# IO_board-ha-v4.net
KiCad netlist of a schematic drawn in EAGLE
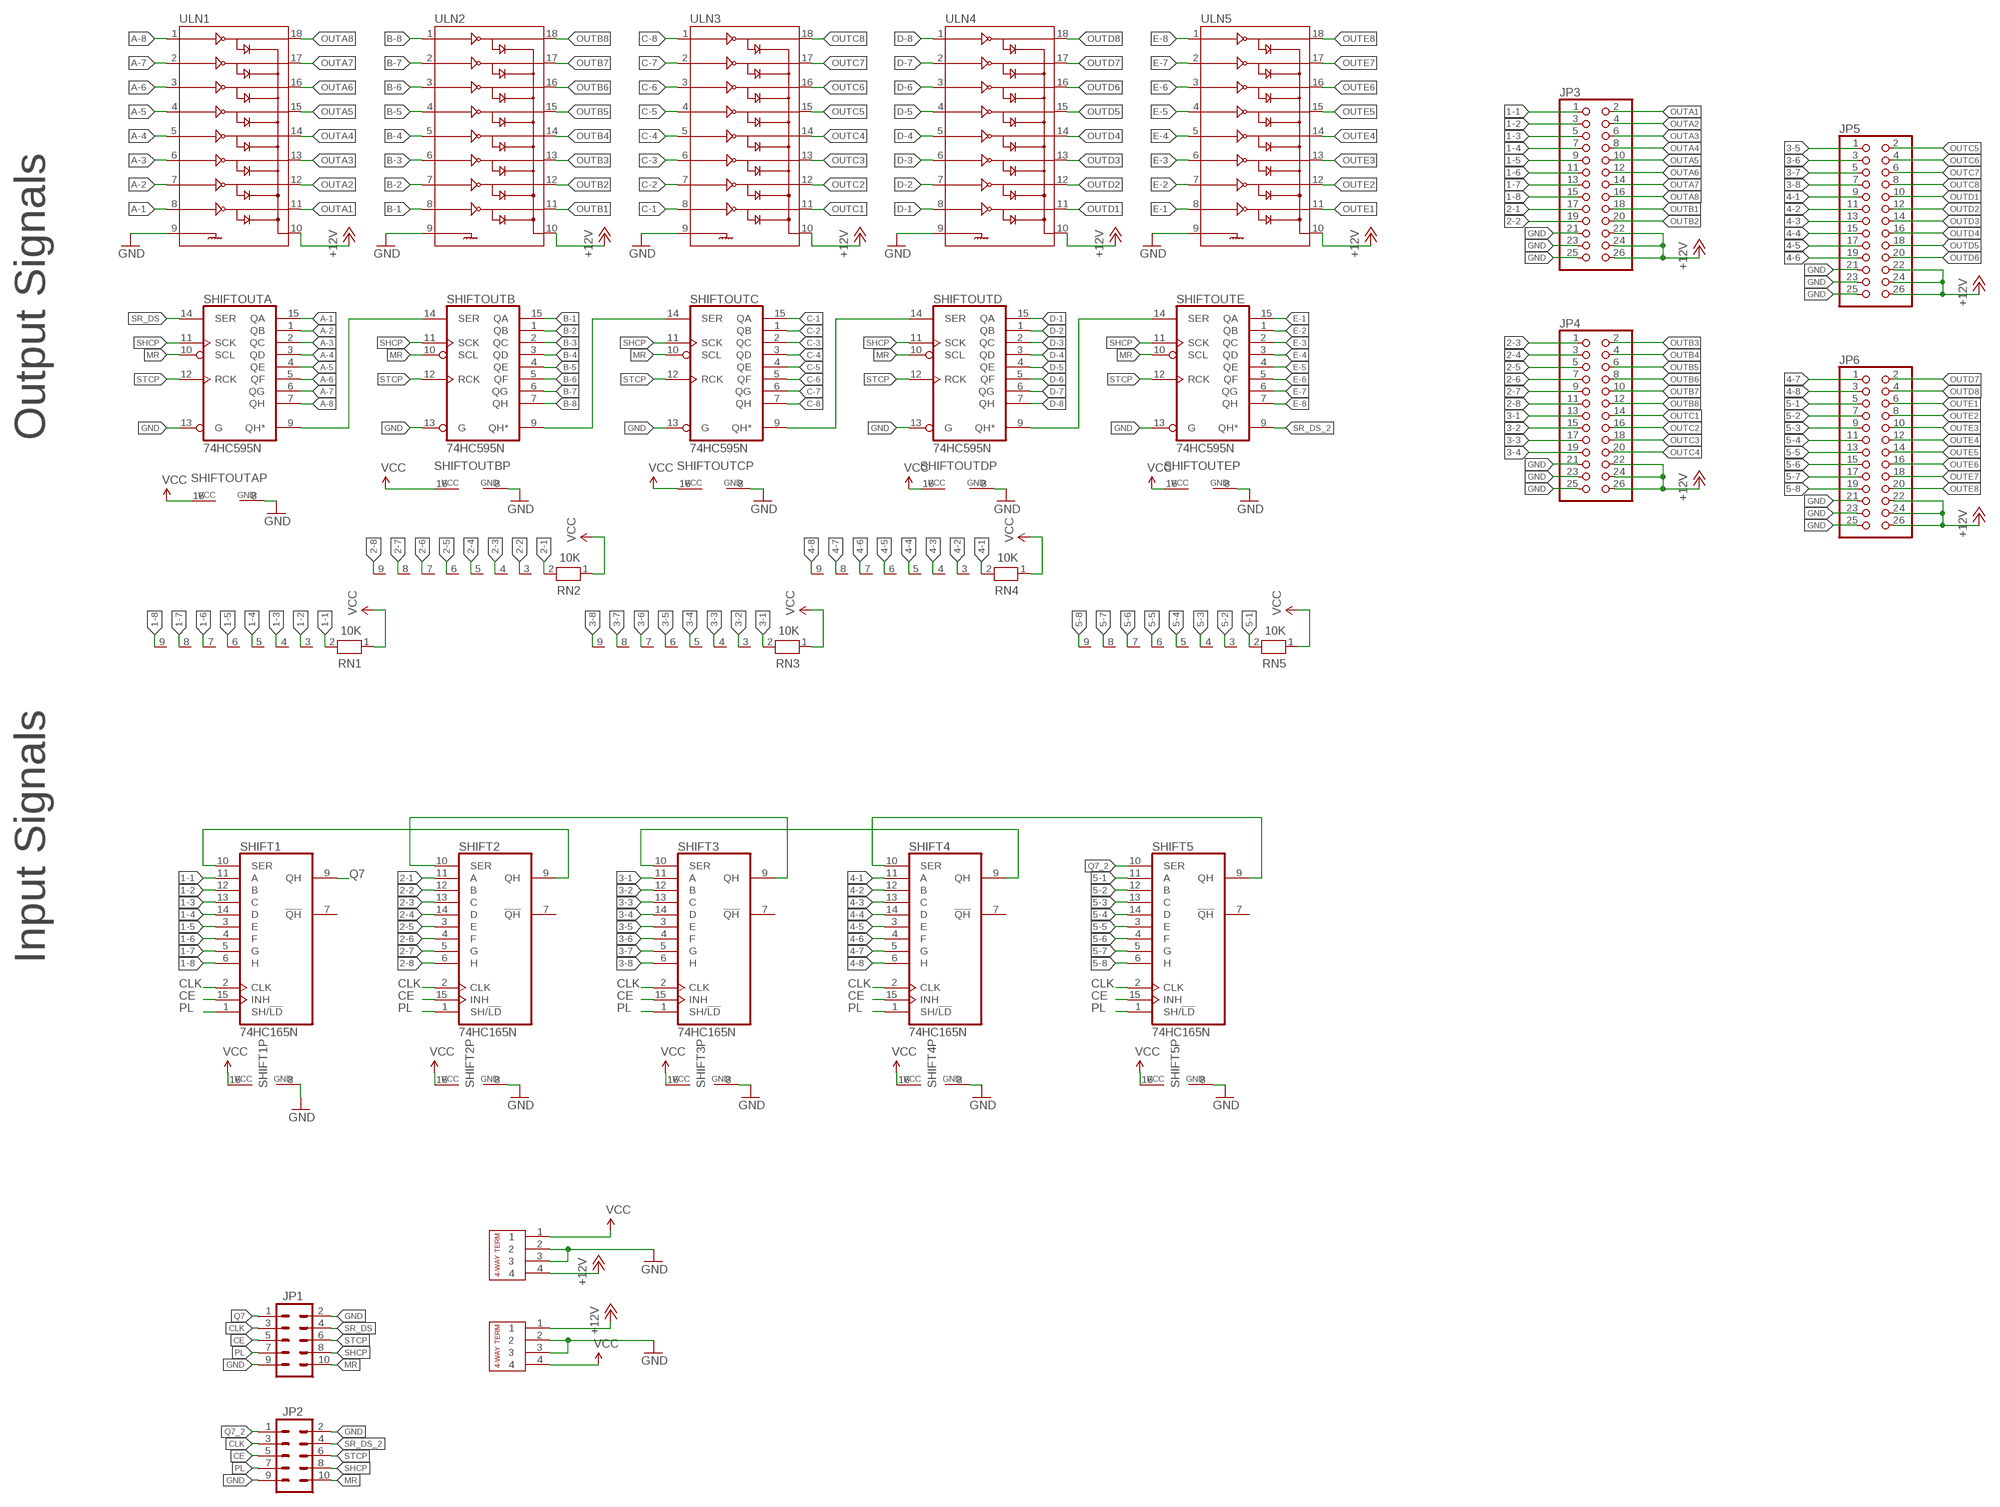
[diagram p0: schematic, sheet 1]

(export (version "E")
  (design (tool "Eeschema 10.0.6"))
  (components
    (comp (ref "J1")
      (value "4-PIN-CON-1759017")
      (footprint "eagle-import:4-PIN-CON-1759017")
      (libsource (lib "eagle-import") (part "4-PIN-CON-1759017"))
    )
    (comp (ref "J2")
      (value "4-PIN-CON-1759017")
      (footprint "eagle-import:4-PIN-CON-1759017")
      (libsource (lib "eagle-import") (part "4-PIN-CON-1759017"))
    )
    (comp (ref "JP1")
      (value "M05X2SHD")
      (footprint "eagle-import:2X5-SHROUDED")
      (libsource (lib "eagle-import") (part "M05X2SHD"))
    )
    (comp (ref "JP2")
      (value "M05X2SHD")
      (footprint "eagle-import:2X5-SHROUDED")
      (libsource (lib "eagle-import") (part "M05X2SHD"))
    )
    (comp (ref "JP3")
      (value "PINHD-2X13")
      (footprint "eagle-import:2X13")
      (libsource (lib "eagle-import") (part "PINHD-2X13"))
    )
    (comp (ref "JP4")
      (value "PINHD-2X13")
      (footprint "eagle-import:2X13")
      (libsource (lib "eagle-import") (part "PINHD-2X13"))
    )
    (comp (ref "JP5")
      (value "PINHD-2X13")
      (footprint "eagle-import:2X13")
      (libsource (lib "eagle-import") (part "PINHD-2X13"))
    )
    (comp (ref "JP6")
      (value "PINHD-2X13")
      (footprint "eagle-import:2X13")
      (libsource (lib "eagle-import") (part "PINHD-2X13"))
    )
    (comp (ref "RN1")
      (value "10K")
      (footprint "eagle-import:RN-9")
      (libsource (lib "eagle-import") (part "RN08"))
    )
    (comp (ref "RN2")
      (value "10K")
      (footprint "eagle-import:RN-9")
      (libsource (lib "eagle-import") (part "RN08"))
    )
    (comp (ref "RN3")
      (value "10K")
      (footprint "eagle-import:RN-9")
      (libsource (lib "eagle-import") (part "RN08"))
    )
    (comp (ref "RN4")
      (value "10K")
      (footprint "eagle-import:RN-9")
      (libsource (lib "eagle-import") (part "RN08"))
    )
    (comp (ref "RN5")
      (value "10K")
      (footprint "eagle-import:RN-9")
      (libsource (lib "eagle-import") (part "RN08"))
    )
    (comp (ref "SHIFT1")
      (value "74HC165N")
      (footprint "eagle-import:DIL16")
      (libsource (lib "eagle-import") (part "74165NHC"))
    )
    (comp (ref "SHIFT2")
      (value "74HC165N")
      (footprint "eagle-import:DIL16")
      (libsource (lib "eagle-import") (part "74165NHC"))
    )
    (comp (ref "SHIFT3")
      (value "74HC165N")
      (footprint "eagle-import:DIL16")
      (libsource (lib "eagle-import") (part "74165NHC"))
    )
    (comp (ref "SHIFT4")
      (value "74HC165N")
      (footprint "eagle-import:DIL16")
      (libsource (lib "eagle-import") (part "74165NHC"))
    )
    (comp (ref "SHIFT5")
      (value "74HC165N")
      (footprint "eagle-import:DIL16")
      (libsource (lib "eagle-import") (part "74165NHC"))
    )
    (comp (ref "SHIFTOUTA")
      (value "74HC595N")
      (footprint "eagle-import:DIL16")
      (libsource (lib "eagle-import") (part "74595NHC"))
    )
    (comp (ref "SHIFTOUTB")
      (value "74HC595N")
      (footprint "eagle-import:DIL16")
      (libsource (lib "eagle-import") (part "74595NHC"))
    )
    (comp (ref "SHIFTOUTC")
      (value "74HC595N")
      (footprint "eagle-import:DIL16")
      (libsource (lib "eagle-import") (part "74595NHC"))
    )
    (comp (ref "SHIFTOUTD")
      (value "74HC595N")
      (footprint "eagle-import:DIL16")
      (libsource (lib "eagle-import") (part "74595NHC"))
    )
    (comp (ref "SHIFTOUTE")
      (value "74HC595N")
      (footprint "eagle-import:DIL16")
      (libsource (lib "eagle-import") (part "74595NHC"))
    )
    (comp (ref "ULN1")
      (value "ULN2803DIP")
      (footprint "eagle-import:DIL18")
      (libsource (lib "eagle-import") (part "ULN2803DIP"))
    )
    (comp (ref "ULN2")
      (value "ULN2803DIP")
      (footprint "eagle-import:DIL18")
      (libsource (lib "eagle-import") (part "ULN2803DIP"))
    )
    (comp (ref "ULN3")
      (value "ULN2803DIP")
      (footprint "eagle-import:DIL18")
      (libsource (lib "eagle-import") (part "ULN2803DIP"))
    )
    (comp (ref "ULN4")
      (value "ULN2803DIP")
      (footprint "eagle-import:DIL18")
      (libsource (lib "eagle-import") (part "ULN2803DIP"))
    )
    (comp (ref "ULN5")
      (value "ULN2803DIP")
      (footprint "eagle-import:DIL18")
      (libsource (lib "eagle-import") (part "ULN2803DIP"))
    )
  )
  (nets
    (net (code "1") (name "+12V") (class "Default")
      (node (ref "J1") (pin "4") (pinfunction "4_4") (pintype "bidirectional"))
      (node (ref "J2") (pin "1") (pinfunction "1_1") (pintype "bidirectional"))
      (node (ref "JP3") (pin "22") (pinfunction "22_22") (pintype "passive"))
      (node (ref "JP3") (pin "24") (pinfunction "24_24") (pintype "passive"))
      (node (ref "JP3") (pin "26") (pinfunction "26_26") (pintype "passive"))
      (node (ref "JP4") (pin "22") (pinfunction "22_22") (pintype "passive"))
      (node (ref "JP4") (pin "24") (pinfunction "24_24") (pintype "passive"))
      (node (ref "JP4") (pin "26") (pinfunction "26_26") (pintype "passive"))
      (node (ref "JP5") (pin "22") (pinfunction "22_22") (pintype "passive"))
      (node (ref "JP5") (pin "24") (pinfunction "24_24") (pintype "passive"))
      (node (ref "JP5") (pin "26") (pinfunction "26_26") (pintype "passive"))
      (node (ref "JP6") (pin "22") (pinfunction "22_22") (pintype "passive"))
      (node (ref "JP6") (pin "24") (pinfunction "24_24") (pintype "passive"))
      (node (ref "JP6") (pin "26") (pinfunction "26_26") (pintype "passive"))
      (node (ref "ULN1") (pin "10") (pinfunction "10_10") (pintype "bidirectional"))
      (node (ref "ULN2") (pin "10") (pinfunction "10_10") (pintype "bidirectional"))
      (node (ref "ULN3") (pin "10") (pinfunction "10_10") (pintype "bidirectional"))
      (node (ref "ULN4") (pin "10") (pinfunction "10_10") (pintype "bidirectional"))
      (node (ref "ULN5") (pin "10") (pinfunction "10_10") (pintype "bidirectional"))
    )
    (net (code "2") (name "1-1") (class "Default")
      (node (ref "JP3") (pin "1") (pinfunction "1_1") (pintype "passive"))
      (node (ref "RN1") (pin "2") (pinfunction "2_2") (pintype "passive"))
      (node (ref "SHIFT1") (pin "11") (pinfunction "A_11") (pintype "input"))
    )
    (net (code "3") (name "1-2") (class "Default")
      (node (ref "JP3") (pin "3") (pinfunction "3_3") (pintype "passive"))
      (node (ref "RN1") (pin "3") (pinfunction "3_3") (pintype "passive"))
      (node (ref "SHIFT1") (pin "12") (pinfunction "B_12") (pintype "input"))
    )
    (net (code "4") (name "1-3") (class "Default")
      (node (ref "JP3") (pin "5") (pinfunction "5_5") (pintype "passive"))
      (node (ref "RN1") (pin "4") (pinfunction "4_4") (pintype "passive"))
      (node (ref "SHIFT1") (pin "13") (pinfunction "C_13") (pintype "input"))
    )
    (net (code "5") (name "1-4") (class "Default")
      (node (ref "JP3") (pin "7") (pinfunction "7_7") (pintype "passive"))
      (node (ref "RN1") (pin "5") (pinfunction "5_5") (pintype "passive"))
      (node (ref "SHIFT1") (pin "14") (pinfunction "D_14") (pintype "input"))
    )
    (net (code "6") (name "1-5") (class "Default")
      (node (ref "JP3") (pin "9") (pinfunction "9_9") (pintype "passive"))
      (node (ref "RN1") (pin "6") (pinfunction "6_6") (pintype "passive"))
      (node (ref "SHIFT1") (pin "3") (pinfunction "E_3") (pintype "input"))
    )
    (net (code "7") (name "1-6") (class "Default")
      (node (ref "JP3") (pin "11") (pinfunction "11_11") (pintype "passive"))
      (node (ref "RN1") (pin "7") (pinfunction "7_7") (pintype "passive"))
      (node (ref "SHIFT1") (pin "4") (pinfunction "F_4") (pintype "input"))
    )
    (net (code "8") (name "1-7") (class "Default")
      (node (ref "JP3") (pin "13") (pinfunction "13_13") (pintype "passive"))
      (node (ref "RN1") (pin "8") (pinfunction "8_8") (pintype "passive"))
      (node (ref "SHIFT1") (pin "5") (pinfunction "G_5") (pintype "input"))
    )
    (net (code "9") (name "1-8") (class "Default")
      (node (ref "JP3") (pin "15") (pinfunction "15_15") (pintype "passive"))
      (node (ref "RN1") (pin "9") (pinfunction "9_9") (pintype "passive"))
      (node (ref "SHIFT1") (pin "6") (pinfunction "H_6") (pintype "input"))
    )
    (net (code "10") (name "2-1") (class "Default")
      (node (ref "JP3") (pin "17") (pinfunction "17_17") (pintype "passive"))
      (node (ref "RN2") (pin "2") (pinfunction "2_2") (pintype "passive"))
      (node (ref "SHIFT2") (pin "11") (pinfunction "A_11") (pintype "input"))
    )
    (net (code "11") (name "2-2") (class "Default")
      (node (ref "JP3") (pin "19") (pinfunction "19_19") (pintype "passive"))
      (node (ref "RN2") (pin "3") (pinfunction "3_3") (pintype "passive"))
      (node (ref "SHIFT2") (pin "12") (pinfunction "B_12") (pintype "input"))
    )
    (net (code "12") (name "2-3") (class "Default")
      (node (ref "JP4") (pin "1") (pinfunction "1_1") (pintype "passive"))
      (node (ref "RN2") (pin "4") (pinfunction "4_4") (pintype "passive"))
      (node (ref "SHIFT2") (pin "13") (pinfunction "C_13") (pintype "input"))
    )
    (net (code "13") (name "2-4") (class "Default")
      (node (ref "JP4") (pin "3") (pinfunction "3_3") (pintype "passive"))
      (node (ref "RN2") (pin "5") (pinfunction "5_5") (pintype "passive"))
      (node (ref "SHIFT2") (pin "14") (pinfunction "D_14") (pintype "input"))
    )
    (net (code "14") (name "2-5") (class "Default")
      (node (ref "JP4") (pin "5") (pinfunction "5_5") (pintype "passive"))
      (node (ref "RN2") (pin "6") (pinfunction "6_6") (pintype "passive"))
      (node (ref "SHIFT2") (pin "3") (pinfunction "E_3") (pintype "input"))
    )
    (net (code "15") (name "2-6") (class "Default")
      (node (ref "JP4") (pin "7") (pinfunction "7_7") (pintype "passive"))
      (node (ref "RN2") (pin "7") (pinfunction "7_7") (pintype "passive"))
      (node (ref "SHIFT2") (pin "4") (pinfunction "F_4") (pintype "input"))
    )
    (net (code "16") (name "2-7") (class "Default")
      (node (ref "JP4") (pin "9") (pinfunction "9_9") (pintype "passive"))
      (node (ref "RN2") (pin "8") (pinfunction "8_8") (pintype "passive"))
      (node (ref "SHIFT2") (pin "5") (pinfunction "G_5") (pintype "input"))
    )
    (net (code "17") (name "2-8") (class "Default")
      (node (ref "JP4") (pin "11") (pinfunction "11_11") (pintype "passive"))
      (node (ref "RN2") (pin "9") (pinfunction "9_9") (pintype "passive"))
      (node (ref "SHIFT2") (pin "6") (pinfunction "H_6") (pintype "input"))
    )
    (net (code "18") (name "3-1") (class "Default")
      (node (ref "JP4") (pin "13") (pinfunction "13_13") (pintype "passive"))
      (node (ref "RN3") (pin "2") (pinfunction "2_2") (pintype "passive"))
      (node (ref "SHIFT3") (pin "11") (pinfunction "A_11") (pintype "input"))
    )
    (net (code "19") (name "3-2") (class "Default")
      (node (ref "JP4") (pin "15") (pinfunction "15_15") (pintype "passive"))
      (node (ref "RN3") (pin "3") (pinfunction "3_3") (pintype "passive"))
      (node (ref "SHIFT3") (pin "12") (pinfunction "B_12") (pintype "input"))
    )
    (net (code "20") (name "3-3") (class "Default")
      (node (ref "JP4") (pin "17") (pinfunction "17_17") (pintype "passive"))
      (node (ref "RN3") (pin "4") (pinfunction "4_4") (pintype "passive"))
      (node (ref "SHIFT3") (pin "13") (pinfunction "C_13") (pintype "input"))
    )
    (net (code "21") (name "3-4") (class "Default")
      (node (ref "JP4") (pin "19") (pinfunction "19_19") (pintype "passive"))
      (node (ref "RN3") (pin "5") (pinfunction "5_5") (pintype "passive"))
      (node (ref "SHIFT3") (pin "14") (pinfunction "D_14") (pintype "input"))
    )
    (net (code "22") (name "3-5") (class "Default")
      (node (ref "JP5") (pin "1") (pinfunction "1_1") (pintype "passive"))
      (node (ref "RN3") (pin "6") (pinfunction "6_6") (pintype "passive"))
      (node (ref "SHIFT3") (pin "3") (pinfunction "E_3") (pintype "input"))
    )
    (net (code "23") (name "3-6") (class "Default")
      (node (ref "JP5") (pin "3") (pinfunction "3_3") (pintype "passive"))
      (node (ref "RN3") (pin "7") (pinfunction "7_7") (pintype "passive"))
      (node (ref "SHIFT3") (pin "4") (pinfunction "F_4") (pintype "input"))
    )
    (net (code "24") (name "3-7") (class "Default")
      (node (ref "JP5") (pin "5") (pinfunction "5_5") (pintype "passive"))
      (node (ref "RN3") (pin "8") (pinfunction "8_8") (pintype "passive"))
      (node (ref "SHIFT3") (pin "5") (pinfunction "G_5") (pintype "input"))
    )
    (net (code "25") (name "3-8") (class "Default")
      (node (ref "JP5") (pin "7") (pinfunction "7_7") (pintype "passive"))
      (node (ref "RN3") (pin "9") (pinfunction "9_9") (pintype "passive"))
      (node (ref "SHIFT3") (pin "6") (pinfunction "H_6") (pintype "input"))
    )
    (net (code "26") (name "4-1") (class "Default")
      (node (ref "JP5") (pin "9") (pinfunction "9_9") (pintype "passive"))
      (node (ref "RN4") (pin "2") (pinfunction "2_2") (pintype "passive"))
      (node (ref "SHIFT4") (pin "11") (pinfunction "A_11") (pintype "input"))
    )
    (net (code "27") (name "4-2") (class "Default")
      (node (ref "JP5") (pin "11") (pinfunction "11_11") (pintype "passive"))
      (node (ref "RN4") (pin "3") (pinfunction "3_3") (pintype "passive"))
      (node (ref "SHIFT4") (pin "12") (pinfunction "B_12") (pintype "input"))
    )
    (net (code "28") (name "4-3") (class "Default")
      (node (ref "JP5") (pin "13") (pinfunction "13_13") (pintype "passive"))
      (node (ref "RN4") (pin "4") (pinfunction "4_4") (pintype "passive"))
      (node (ref "SHIFT4") (pin "13") (pinfunction "C_13") (pintype "input"))
    )
    (net (code "29") (name "4-4") (class "Default")
      (node (ref "JP5") (pin "15") (pinfunction "15_15") (pintype "passive"))
      (node (ref "RN4") (pin "5") (pinfunction "5_5") (pintype "passive"))
      (node (ref "SHIFT4") (pin "14") (pinfunction "D_14") (pintype "input"))
    )
    (net (code "30") (name "4-5") (class "Default")
      (node (ref "JP5") (pin "17") (pinfunction "17_17") (pintype "passive"))
      (node (ref "RN4") (pin "6") (pinfunction "6_6") (pintype "passive"))
      (node (ref "SHIFT4") (pin "3") (pinfunction "E_3") (pintype "input"))
    )
    (net (code "31") (name "4-6") (class "Default")
      (node (ref "JP5") (pin "19") (pinfunction "19_19") (pintype "passive"))
      (node (ref "RN4") (pin "7") (pinfunction "7_7") (pintype "passive"))
      (node (ref "SHIFT4") (pin "4") (pinfunction "F_4") (pintype "input"))
    )
    (net (code "32") (name "4-7") (class "Default")
      (node (ref "JP6") (pin "1") (pinfunction "1_1") (pintype "passive"))
      (node (ref "RN4") (pin "8") (pinfunction "8_8") (pintype "passive"))
      (node (ref "SHIFT4") (pin "5") (pinfunction "G_5") (pintype "input"))
    )
    (net (code "33") (name "4-8") (class "Default")
      (node (ref "JP6") (pin "3") (pinfunction "3_3") (pintype "passive"))
      (node (ref "RN4") (pin "9") (pinfunction "9_9") (pintype "passive"))
      (node (ref "SHIFT4") (pin "6") (pinfunction "H_6") (pintype "input"))
    )
    (net (code "34") (name "5-1") (class "Default")
      (node (ref "JP6") (pin "5") (pinfunction "5_5") (pintype "passive"))
      (node (ref "RN5") (pin "2") (pinfunction "2_2") (pintype "passive"))
      (node (ref "SHIFT5") (pin "11") (pinfunction "A_11") (pintype "input"))
    )
    (net (code "35") (name "5-2") (class "Default")
      (node (ref "JP6") (pin "7") (pinfunction "7_7") (pintype "passive"))
      (node (ref "RN5") (pin "3") (pinfunction "3_3") (pintype "passive"))
      (node (ref "SHIFT5") (pin "12") (pinfunction "B_12") (pintype "input"))
    )
    (net (code "36") (name "5-3") (class "Default")
      (node (ref "JP6") (pin "9") (pinfunction "9_9") (pintype "passive"))
      (node (ref "RN5") (pin "4") (pinfunction "4_4") (pintype "passive"))
      (node (ref "SHIFT5") (pin "13") (pinfunction "C_13") (pintype "input"))
    )
    (net (code "37") (name "5-4") (class "Default")
      (node (ref "JP6") (pin "11") (pinfunction "11_11") (pintype "passive"))
      (node (ref "RN5") (pin "5") (pinfunction "5_5") (pintype "passive"))
      (node (ref "SHIFT5") (pin "14") (pinfunction "D_14") (pintype "input"))
    )
    (net (code "38") (name "5-5") (class "Default")
      (node (ref "JP6") (pin "13") (pinfunction "13_13") (pintype "passive"))
      (node (ref "RN5") (pin "6") (pinfunction "6_6") (pintype "passive"))
      (node (ref "SHIFT5") (pin "3") (pinfunction "E_3") (pintype "input"))
    )
    (net (code "39") (name "5-6") (class "Default")
      (node (ref "JP6") (pin "15") (pinfunction "15_15") (pintype "passive"))
      (node (ref "RN5") (pin "7") (pinfunction "7_7") (pintype "passive"))
      (node (ref "SHIFT5") (pin "4") (pinfunction "F_4") (pintype "input"))
    )
    (net (code "40") (name "5-7") (class "Default")
      (node (ref "JP6") (pin "17") (pinfunction "17_17") (pintype "passive"))
      (node (ref "RN5") (pin "8") (pinfunction "8_8") (pintype "passive"))
      (node (ref "SHIFT5") (pin "5") (pinfunction "G_5") (pintype "input"))
    )
    (net (code "41") (name "5-8") (class "Default")
      (node (ref "JP6") (pin "19") (pinfunction "19_19") (pintype "passive"))
      (node (ref "RN5") (pin "9") (pinfunction "9_9") (pintype "passive"))
      (node (ref "SHIFT5") (pin "6") (pinfunction "H_6") (pintype "input"))
    )
    (net (code "42") (name "A-1") (class "Default")
      (node (ref "SHIFTOUTA") (pin "15") (pinfunction "QA_15") (pintype "tri_state"))
      (node (ref "ULN1") (pin "8") (pinfunction "8_8") (pintype "bidirectional"))
    )
    (net (code "43") (name "A-2") (class "Default")
      (node (ref "SHIFTOUTA") (pin "1") (pinfunction "QB_1") (pintype "tri_state"))
      (node (ref "ULN1") (pin "7") (pinfunction "7_7") (pintype "bidirectional"))
    )
    (net (code "44") (name "A-3") (class "Default")
      (node (ref "SHIFTOUTA") (pin "2") (pinfunction "QC_2") (pintype "tri_state"))
      (node (ref "ULN1") (pin "6") (pinfunction "6_6") (pintype "bidirectional"))
    )
    (net (code "45") (name "A-4") (class "Default")
      (node (ref "SHIFTOUTA") (pin "3") (pinfunction "QD_3") (pintype "tri_state"))
      (node (ref "ULN1") (pin "5") (pinfunction "5_5") (pintype "bidirectional"))
    )
    (net (code "46") (name "A-5") (class "Default")
      (node (ref "SHIFTOUTA") (pin "4") (pinfunction "QE_4") (pintype "tri_state"))
      (node (ref "ULN1") (pin "4") (pinfunction "4_4") (pintype "bidirectional"))
    )
    (net (code "47") (name "A-6") (class "Default")
      (node (ref "SHIFTOUTA") (pin "5") (pinfunction "QF_5") (pintype "tri_state"))
      (node (ref "ULN1") (pin "3") (pinfunction "3_3") (pintype "bidirectional"))
    )
    (net (code "48") (name "A-7") (class "Default")
      (node (ref "SHIFTOUTA") (pin "6") (pinfunction "QG_6") (pintype "tri_state"))
      (node (ref "ULN1") (pin "2") (pinfunction "2_2") (pintype "bidirectional"))
    )
    (net (code "49") (name "A-8") (class "Default")
      (node (ref "SHIFTOUTA") (pin "7") (pinfunction "QH_7") (pintype "tri_state"))
      (node (ref "ULN1") (pin "1") (pinfunction "1_1") (pintype "bidirectional"))
    )
    (net (code "50") (name "B-1") (class "Default")
      (node (ref "SHIFTOUTB") (pin "15") (pinfunction "QA_15") (pintype "tri_state"))
      (node (ref "ULN2") (pin "8") (pinfunction "8_8") (pintype "bidirectional"))
    )
    (net (code "51") (name "B-2") (class "Default")
      (node (ref "SHIFTOUTB") (pin "1") (pinfunction "QB_1") (pintype "tri_state"))
      (node (ref "ULN2") (pin "7") (pinfunction "7_7") (pintype "bidirectional"))
    )
    (net (code "52") (name "B-3") (class "Default")
      (node (ref "SHIFTOUTB") (pin "2") (pinfunction "QC_2") (pintype "tri_state"))
      (node (ref "ULN2") (pin "6") (pinfunction "6_6") (pintype "bidirectional"))
    )
    (net (code "53") (name "B-4") (class "Default")
      (node (ref "SHIFTOUTB") (pin "3") (pinfunction "QD_3") (pintype "tri_state"))
      (node (ref "ULN2") (pin "5") (pinfunction "5_5") (pintype "bidirectional"))
    )
    (net (code "54") (name "B-5") (class "Default")
      (node (ref "SHIFTOUTB") (pin "4") (pinfunction "QE_4") (pintype "tri_state"))
      (node (ref "ULN2") (pin "4") (pinfunction "4_4") (pintype "bidirectional"))
    )
    (net (code "55") (name "B-6") (class "Default")
      (node (ref "SHIFTOUTB") (pin "5") (pinfunction "QF_5") (pintype "tri_state"))
      (node (ref "ULN2") (pin "3") (pinfunction "3_3") (pintype "bidirectional"))
    )
    (net (code "56") (name "B-7") (class "Default")
      (node (ref "SHIFTOUTB") (pin "6") (pinfunction "QG_6") (pintype "tri_state"))
      (node (ref "ULN2") (pin "2") (pinfunction "2_2") (pintype "bidirectional"))
    )
    (net (code "57") (name "B-8") (class "Default")
      (node (ref "SHIFTOUTB") (pin "7") (pinfunction "QH_7") (pintype "tri_state"))
      (node (ref "ULN2") (pin "1") (pinfunction "1_1") (pintype "bidirectional"))
    )
    (net (code "58") (name "C-1") (class "Default")
      (node (ref "SHIFTOUTC") (pin "15") (pinfunction "QA_15") (pintype "tri_state"))
      (node (ref "ULN3") (pin "8") (pinfunction "8_8") (pintype "bidirectional"))
    )
    (net (code "59") (name "C-2") (class "Default")
      (node (ref "SHIFTOUTC") (pin "1") (pinfunction "QB_1") (pintype "tri_state"))
      (node (ref "ULN3") (pin "7") (pinfunction "7_7") (pintype "bidirectional"))
    )
    (net (code "60") (name "C-3") (class "Default")
      (node (ref "SHIFTOUTC") (pin "2") (pinfunction "QC_2") (pintype "tri_state"))
      (node (ref "ULN3") (pin "6") (pinfunction "6_6") (pintype "bidirectional"))
    )
    (net (code "61") (name "C-4") (class "Default")
      (node (ref "SHIFTOUTC") (pin "3") (pinfunction "QD_3") (pintype "tri_state"))
      (node (ref "ULN3") (pin "5") (pinfunction "5_5") (pintype "bidirectional"))
    )
    (net (code "62") (name "C-5") (class "Default")
      (node (ref "SHIFTOUTC") (pin "4") (pinfunction "QE_4") (pintype "tri_state"))
      (node (ref "ULN3") (pin "4") (pinfunction "4_4") (pintype "bidirectional"))
    )
    (net (code "63") (name "C-6") (class "Default")
      (node (ref "SHIFTOUTC") (pin "5") (pinfunction "QF_5") (pintype "tri_state"))
      (node (ref "ULN3") (pin "3") (pinfunction "3_3") (pintype "bidirectional"))
    )
    (net (code "64") (name "C-7") (class "Default")
      (node (ref "SHIFTOUTC") (pin "6") (pinfunction "QG_6") (pintype "tri_state"))
      (node (ref "ULN3") (pin "2") (pinfunction "2_2") (pintype "bidirectional"))
    )
    (net (code "65") (name "C-8") (class "Default")
      (node (ref "SHIFTOUTC") (pin "7") (pinfunction "QH_7") (pintype "tri_state"))
      (node (ref "ULN3") (pin "1") (pinfunction "1_1") (pintype "bidirectional"))
    )
    (net (code "66") (name "CE") (class "Default")
      (node (ref "JP1") (pin "5") (pinfunction "5_5") (pintype "passive"))
      (node (ref "JP2") (pin "5") (pinfunction "5_5") (pintype "passive"))
      (node (ref "SHIFT1") (pin "15") (pinfunction "INH_15") (pintype "input"))
      (node (ref "SHIFT2") (pin "15") (pinfunction "INH_15") (pintype "input"))
      (node (ref "SHIFT3") (pin "15") (pinfunction "INH_15") (pintype "input"))
      (node (ref "SHIFT4") (pin "15") (pinfunction "INH_15") (pintype "input"))
      (node (ref "SHIFT5") (pin "15") (pinfunction "INH_15") (pintype "input"))
    )
    (net (code "67") (name "CLK") (class "Default")
      (node (ref "JP1") (pin "3") (pinfunction "3_3") (pintype "passive"))
      (node (ref "JP2") (pin "3") (pinfunction "3_3") (pintype "passive"))
      (node (ref "SHIFT1") (pin "2") (pinfunction "CLK_2") (pintype "input"))
      (node (ref "SHIFT2") (pin "2") (pinfunction "CLK_2") (pintype "input"))
      (node (ref "SHIFT3") (pin "2") (pinfunction "CLK_2") (pintype "input"))
      (node (ref "SHIFT4") (pin "2") (pinfunction "CLK_2") (pintype "input"))
      (node (ref "SHIFT5") (pin "2") (pinfunction "CLK_2") (pintype "input"))
    )
    (net (code "68") (name "D-1") (class "Default")
      (node (ref "SHIFTOUTD") (pin "15") (pinfunction "QA_15") (pintype "tri_state"))
      (node (ref "ULN4") (pin "8") (pinfunction "8_8") (pintype "bidirectional"))
    )
    (net (code "69") (name "D-2") (class "Default")
      (node (ref "SHIFTOUTD") (pin "1") (pinfunction "QB_1") (pintype "tri_state"))
      (node (ref "ULN4") (pin "7") (pinfunction "7_7") (pintype "bidirectional"))
    )
    (net (code "70") (name "D-3") (class "Default")
      (node (ref "SHIFTOUTD") (pin "2") (pinfunction "QC_2") (pintype "tri_state"))
      (node (ref "ULN4") (pin "6") (pinfunction "6_6") (pintype "bidirectional"))
    )
    (net (code "71") (name "D-4") (class "Default")
      (node (ref "SHIFTOUTD") (pin "3") (pinfunction "QD_3") (pintype "tri_state"))
      (node (ref "ULN4") (pin "5") (pinfunction "5_5") (pintype "bidirectional"))
    )
    (net (code "72") (name "D-5") (class "Default")
      (node (ref "SHIFTOUTD") (pin "4") (pinfunction "QE_4") (pintype "tri_state"))
      (node (ref "ULN4") (pin "4") (pinfunction "4_4") (pintype "bidirectional"))
    )
    (net (code "73") (name "D-6") (class "Default")
      (node (ref "SHIFTOUTD") (pin "5") (pinfunction "QF_5") (pintype "tri_state"))
      (node (ref "ULN4") (pin "3") (pinfunction "3_3") (pintype "bidirectional"))
    )
    (net (code "74") (name "D-7") (class "Default")
      (node (ref "SHIFTOUTD") (pin "6") (pinfunction "QG_6") (pintype "tri_state"))
      (node (ref "ULN4") (pin "2") (pinfunction "2_2") (pintype "bidirectional"))
    )
    (net (code "75") (name "D-8") (class "Default")
      (node (ref "SHIFTOUTD") (pin "7") (pinfunction "QH_7") (pintype "tri_state"))
      (node (ref "ULN4") (pin "1") (pinfunction "1_1") (pintype "bidirectional"))
    )
    (net (code "76") (name "E-1") (class "Default")
      (node (ref "SHIFTOUTE") (pin "15") (pinfunction "QA_15") (pintype "tri_state"))
      (node (ref "ULN5") (pin "8") (pinfunction "8_8") (pintype "bidirectional"))
    )
    (net (code "77") (name "E-2") (class "Default")
      (node (ref "SHIFTOUTE") (pin "1") (pinfunction "QB_1") (pintype "tri_state"))
      (node (ref "ULN5") (pin "7") (pinfunction "7_7") (pintype "bidirectional"))
    )
    (net (code "78") (name "E-3") (class "Default")
      (node (ref "SHIFTOUTE") (pin "2") (pinfunction "QC_2") (pintype "tri_state"))
      (node (ref "ULN5") (pin "6") (pinfunction "6_6") (pintype "bidirectional"))
    )
    (net (code "79") (name "E-4") (class "Default")
      (node (ref "SHIFTOUTE") (pin "3") (pinfunction "QD_3") (pintype "tri_state"))
      (node (ref "ULN5") (pin "5") (pinfunction "5_5") (pintype "bidirectional"))
    )
    (net (code "80") (name "E-5") (class "Default")
      (node (ref "SHIFTOUTE") (pin "4") (pinfunction "QE_4") (pintype "tri_state"))
      (node (ref "ULN5") (pin "4") (pinfunction "4_4") (pintype "bidirectional"))
    )
    (net (code "81") (name "E-6") (class "Default")
      (node (ref "SHIFTOUTE") (pin "5") (pinfunction "QF_5") (pintype "tri_state"))
      (node (ref "ULN5") (pin "3") (pinfunction "3_3") (pintype "bidirectional"))
    )
    (net (code "82") (name "E-7") (class "Default")
      (node (ref "SHIFTOUTE") (pin "6") (pinfunction "QG_6") (pintype "tri_state"))
      (node (ref "ULN5") (pin "2") (pinfunction "2_2") (pintype "bidirectional"))
    )
    (net (code "83") (name "E-8") (class "Default")
      (node (ref "SHIFTOUTE") (pin "7") (pinfunction "QH_7") (pintype "tri_state"))
      (node (ref "ULN5") (pin "1") (pinfunction "1_1") (pintype "bidirectional"))
    )
    (net (code "84") (name "GND") (class "Default")
      (node (ref "J1") (pin "2") (pinfunction "2_2") (pintype "bidirectional"))
      (node (ref "J1") (pin "3") (pinfunction "3_3") (pintype "bidirectional"))
      (node (ref "J2") (pin "2") (pinfunction "2_2") (pintype "bidirectional"))
      (node (ref "J2") (pin "3") (pinfunction "3_3") (pintype "bidirectional"))
      (node (ref "JP1") (pin "2") (pinfunction "2_2") (pintype "passive"))
      (node (ref "JP1") (pin "9") (pinfunction "9_9") (pintype "passive"))
      (node (ref "JP2") (pin "2") (pinfunction "2_2") (pintype "passive"))
      (node (ref "JP2") (pin "9") (pinfunction "9_9") (pintype "passive"))
      (node (ref "JP3") (pin "21") (pinfunction "21_21") (pintype "passive"))
      (node (ref "JP3") (pin "23") (pinfunction "23_23") (pintype "passive"))
      (node (ref "JP3") (pin "25") (pinfunction "25_25") (pintype "passive"))
      (node (ref "JP4") (pin "21") (pinfunction "21_21") (pintype "passive"))
      (node (ref "JP4") (pin "23") (pinfunction "23_23") (pintype "passive"))
      (node (ref "JP4") (pin "25") (pinfunction "25_25") (pintype "passive"))
      (node (ref "JP5") (pin "21") (pinfunction "21_21") (pintype "passive"))
      (node (ref "JP5") (pin "23") (pinfunction "23_23") (pintype "passive"))
      (node (ref "JP5") (pin "25") (pinfunction "25_25") (pintype "passive"))
      (node (ref "JP6") (pin "21") (pinfunction "21_21") (pintype "passive"))
      (node (ref "JP6") (pin "23") (pinfunction "23_23") (pintype "passive"))
      (node (ref "JP6") (pin "25") (pinfunction "25_25") (pintype "passive"))
      (node (ref "SHIFT1") (pin "8") (pinfunction "GND_8") (pintype "power_in"))
      (node (ref "SHIFT2") (pin "8") (pinfunction "GND_8") (pintype "power_in"))
      (node (ref "SHIFT3") (pin "8") (pinfunction "GND_8") (pintype "power_in"))
      (node (ref "SHIFT4") (pin "8") (pinfunction "GND_8") (pintype "power_in"))
      (node (ref "SHIFT5") (pin "8") (pinfunction "GND_8") (pintype "power_in"))
      (node (ref "SHIFTOUTA") (pin "13") (pinfunction "G_13") (pintype "input"))
      (node (ref "SHIFTOUTA") (pin "8") (pinfunction "GND_8") (pintype "power_in"))
      (node (ref "SHIFTOUTB") (pin "13") (pinfunction "G_13") (pintype "input"))
      (node (ref "SHIFTOUTB") (pin "8") (pinfunction "GND_8") (pintype "power_in"))
      (node (ref "SHIFTOUTC") (pin "13") (pinfunction "G_13") (pintype "input"))
      (node (ref "SHIFTOUTC") (pin "8") (pinfunction "GND_8") (pintype "power_in"))
      (node (ref "SHIFTOUTD") (pin "13") (pinfunction "G_13") (pintype "input"))
      (node (ref "SHIFTOUTD") (pin "8") (pinfunction "GND_8") (pintype "power_in"))
      (node (ref "SHIFTOUTE") (pin "13") (pinfunction "G_13") (pintype "input"))
      (node (ref "SHIFTOUTE") (pin "8") (pinfunction "GND_8") (pintype "power_in"))
      (node (ref "ULN1") (pin "9") (pinfunction "9_9") (pintype "bidirectional"))
      (node (ref "ULN2") (pin "9") (pinfunction "9_9") (pintype "bidirectional"))
      (node (ref "ULN3") (pin "9") (pinfunction "9_9") (pintype "bidirectional"))
      (node (ref "ULN4") (pin "9") (pinfunction "9_9") (pintype "bidirectional"))
      (node (ref "ULN5") (pin "9") (pinfunction "9_9") (pintype "bidirectional"))
    )
    (net (code "85") (name "MR") (class "Default")
      (node (ref "JP1") (pin "10") (pinfunction "10_10") (pintype "passive"))
      (node (ref "JP2") (pin "10") (pinfunction "10_10") (pintype "passive"))
      (node (ref "SHIFTOUTA") (pin "10") (pinfunction "SCL_10") (pintype "input"))
      (node (ref "SHIFTOUTB") (pin "10") (pinfunction "SCL_10") (pintype "input"))
      (node (ref "SHIFTOUTC") (pin "10") (pinfunction "SCL_10") (pintype "input"))
      (node (ref "SHIFTOUTD") (pin "10") (pinfunction "SCL_10") (pintype "input"))
      (node (ref "SHIFTOUTE") (pin "10") (pinfunction "SCL_10") (pintype "input"))
    )
    (net (code "86") (name "Net-(SHIFT1A-SER)") (class "Default")
      (node (ref "SHIFT1") (pin "10") (pinfunction "SER_10") (pintype "input"))
      (node (ref "SHIFT2") (pin "9") (pinfunction "QH_9") (pintype "output"))
    )
    (net (code "87") (name "Net-(SHIFT2A-SER)") (class "Default")
      (node (ref "SHIFT2") (pin "10") (pinfunction "SER_10") (pintype "input"))
      (node (ref "SHIFT3") (pin "9") (pinfunction "QH_9") (pintype "output"))
    )
    (net (code "88") (name "Net-(SHIFT3A-SER)") (class "Default")
      (node (ref "SHIFT3") (pin "10") (pinfunction "SER_10") (pintype "input"))
      (node (ref "SHIFT4") (pin "9") (pinfunction "QH_9") (pintype "output"))
    )
    (net (code "89") (name "Net-(SHIFT4A-SER)") (class "Default")
      (node (ref "SHIFT4") (pin "10") (pinfunction "SER_10") (pintype "input"))
      (node (ref "SHIFT5") (pin "9") (pinfunction "QH_9") (pintype "output"))
    )
    (net (code "90") (name "Net-(SHIFTOUTAA-QH*)") (class "Default")
      (node (ref "SHIFTOUTA") (pin "9") (pinfunction "QH*_9") (pintype "tri_state"))
      (node (ref "SHIFTOUTB") (pin "14") (pinfunction "SER_14") (pintype "input"))
    )
    (net (code "91") (name "Net-(SHIFTOUTBA-QH*)") (class "Default")
      (node (ref "SHIFTOUTB") (pin "9") (pinfunction "QH*_9") (pintype "tri_state"))
      (node (ref "SHIFTOUTC") (pin "14") (pinfunction "SER_14") (pintype "input"))
    )
    (net (code "92") (name "Net-(SHIFTOUTCA-QH*)") (class "Default")
      (node (ref "SHIFTOUTC") (pin "9") (pinfunction "QH*_9") (pintype "tri_state"))
      (node (ref "SHIFTOUTD") (pin "14") (pinfunction "SER_14") (pintype "input"))
    )
    (net (code "93") (name "Net-(SHIFTOUTDA-QH*)") (class "Default")
      (node (ref "SHIFTOUTD") (pin "9") (pinfunction "QH*_9") (pintype "tri_state"))
      (node (ref "SHIFTOUTE") (pin "14") (pinfunction "SER_14") (pintype "input"))
    )
    (net (code "94") (name "OUTA1") (class "Default")
      (node (ref "JP3") (pin "2") (pinfunction "2_2") (pintype "passive"))
      (node (ref "ULN1") (pin "11") (pinfunction "11_11") (pintype "bidirectional"))
    )
    (net (code "95") (name "OUTA2") (class "Default")
      (node (ref "JP3") (pin "4") (pinfunction "4_4") (pintype "passive"))
      (node (ref "ULN1") (pin "12") (pinfunction "12_12") (pintype "bidirectional"))
    )
    (net (code "96") (name "OUTA3") (class "Default")
      (node (ref "JP3") (pin "6") (pinfunction "6_6") (pintype "passive"))
      (node (ref "ULN1") (pin "13") (pinfunction "13_13") (pintype "bidirectional"))
    )
    (net (code "97") (name "OUTA4") (class "Default")
      (node (ref "JP3") (pin "8") (pinfunction "8_8") (pintype "passive"))
      (node (ref "ULN1") (pin "14") (pinfunction "14_14") (pintype "bidirectional"))
    )
    (net (code "98") (name "OUTA5") (class "Default")
      (node (ref "JP3") (pin "10") (pinfunction "10_10") (pintype "passive"))
      (node (ref "ULN1") (pin "15") (pinfunction "15_15") (pintype "bidirectional"))
    )
    (net (code "99") (name "OUTA6") (class "Default")
      (node (ref "JP3") (pin "12") (pinfunction "12_12") (pintype "passive"))
      (node (ref "ULN1") (pin "16") (pinfunction "16_16") (pintype "bidirectional"))
    )
    (net (code "100") (name "OUTA7") (class "Default")
      (node (ref "JP3") (pin "14") (pinfunction "14_14") (pintype "passive"))
      (node (ref "ULN1") (pin "17") (pinfunction "17_17") (pintype "bidirectional"))
    )
    (net (code "101") (name "OUTA8") (class "Default")
      (node (ref "JP3") (pin "16") (pinfunction "16_16") (pintype "passive"))
      (node (ref "ULN1") (pin "18") (pinfunction "18_18") (pintype "bidirectional"))
    )
    (net (code "102") (name "OUTB1") (class "Default")
      (node (ref "JP3") (pin "18") (pinfunction "18_18") (pintype "passive"))
      (node (ref "ULN2") (pin "11") (pinfunction "11_11") (pintype "bidirectional"))
    )
    (net (code "103") (name "OUTB2") (class "Default")
      (node (ref "JP3") (pin "20") (pinfunction "20_20") (pintype "passive"))
      (node (ref "ULN2") (pin "12") (pinfunction "12_12") (pintype "bidirectional"))
    )
    (net (code "104") (name "OUTB3") (class "Default")
      (node (ref "JP4") (pin "2") (pinfunction "2_2") (pintype "passive"))
      (node (ref "ULN2") (pin "13") (pinfunction "13_13") (pintype "bidirectional"))
    )
    (net (code "105") (name "OUTB4") (class "Default")
      (node (ref "JP4") (pin "4") (pinfunction "4_4") (pintype "passive"))
      (node (ref "ULN2") (pin "14") (pinfunction "14_14") (pintype "bidirectional"))
    )
    (net (code "106") (name "OUTB5") (class "Default")
      (node (ref "JP4") (pin "6") (pinfunction "6_6") (pintype "passive"))
      (node (ref "ULN2") (pin "15") (pinfunction "15_15") (pintype "bidirectional"))
    )
    (net (code "107") (name "OUTB6") (class "Default")
      (node (ref "JP4") (pin "8") (pinfunction "8_8") (pintype "passive"))
      (node (ref "ULN2") (pin "16") (pinfunction "16_16") (pintype "bidirectional"))
    )
    (net (code "108") (name "OUTB7") (class "Default")
      (node (ref "JP4") (pin "10") (pinfunction "10_10") (pintype "passive"))
      (node (ref "ULN2") (pin "17") (pinfunction "17_17") (pintype "bidirectional"))
    )
    (net (code "109") (name "OUTB8") (class "Default")
      (node (ref "JP4") (pin "12") (pinfunction "12_12") (pintype "passive"))
      (node (ref "ULN2") (pin "18") (pinfunction "18_18") (pintype "bidirectional"))
    )
    (net (code "110") (name "OUTC1") (class "Default")
      (node (ref "JP4") (pin "14") (pinfunction "14_14") (pintype "passive"))
      (node (ref "ULN3") (pin "11") (pinfunction "11_11") (pintype "bidirectional"))
    )
    (net (code "111") (name "OUTC2") (class "Default")
      (node (ref "JP4") (pin "16") (pinfunction "16_16") (pintype "passive"))
      (node (ref "ULN3") (pin "12") (pinfunction "12_12") (pintype "bidirectional"))
    )
    (net (code "112") (name "OUTC3") (class "Default")
      (node (ref "JP4") (pin "18") (pinfunction "18_18") (pintype "passive"))
      (node (ref "ULN3") (pin "13") (pinfunction "13_13") (pintype "bidirectional"))
    )
    (net (code "113") (name "OUTC4") (class "Default")
      (node (ref "JP4") (pin "20") (pinfunction "20_20") (pintype "passive"))
      (node (ref "ULN3") (pin "14") (pinfunction "14_14") (pintype "bidirectional"))
    )
    (net (code "114") (name "OUTC5") (class "Default")
      (node (ref "JP5") (pin "2") (pinfunction "2_2") (pintype "passive"))
      (node (ref "ULN3") (pin "15") (pinfunction "15_15") (pintype "bidirectional"))
    )
    (net (code "115") (name "OUTC6") (class "Default")
      (node (ref "JP5") (pin "4") (pinfunction "4_4") (pintype "passive"))
      (node (ref "ULN3") (pin "16") (pinfunction "16_16") (pintype "bidirectional"))
    )
    (net (code "116") (name "OUTC7") (class "Default")
      (node (ref "JP5") (pin "6") (pinfunction "6_6") (pintype "passive"))
      (node (ref "ULN3") (pin "17") (pinfunction "17_17") (pintype "bidirectional"))
    )
    (net (code "117") (name "OUTC8") (class "Default")
      (node (ref "JP5") (pin "8") (pinfunction "8_8") (pintype "passive"))
      (node (ref "ULN3") (pin "18") (pinfunction "18_18") (pintype "bidirectional"))
    )
    (net (code "118") (name "OUTD1") (class "Default")
      (node (ref "JP5") (pin "10") (pinfunction "10_10") (pintype "passive"))
      (node (ref "ULN4") (pin "11") (pinfunction "11_11") (pintype "bidirectional"))
    )
    (net (code "119") (name "OUTD2") (class "Default")
      (node (ref "JP5") (pin "12") (pinfunction "12_12") (pintype "passive"))
      (node (ref "ULN4") (pin "12") (pinfunction "12_12") (pintype "bidirectional"))
    )
    (net (code "120") (name "OUTD3") (class "Default")
      (node (ref "JP5") (pin "14") (pinfunction "14_14") (pintype "passive"))
      (node (ref "ULN4") (pin "13") (pinfunction "13_13") (pintype "bidirectional"))
    )
    (net (code "121") (name "OUTD4") (class "Default")
      (node (ref "JP5") (pin "16") (pinfunction "16_16") (pintype "passive"))
      (node (ref "ULN4") (pin "14") (pinfunction "14_14") (pintype "bidirectional"))
    )
    (net (code "122") (name "OUTD5") (class "Default")
      (node (ref "JP5") (pin "18") (pinfunction "18_18") (pintype "passive"))
      (node (ref "ULN4") (pin "15") (pinfunction "15_15") (pintype "bidirectional"))
    )
    (net (code "123") (name "OUTD6") (class "Default")
      (node (ref "JP5") (pin "20") (pinfunction "20_20") (pintype "passive"))
      (node (ref "ULN4") (pin "16") (pinfunction "16_16") (pintype "bidirectional"))
    )
    (net (code "124") (name "OUTD7") (class "Default")
      (node (ref "JP6") (pin "2") (pinfunction "2_2") (pintype "passive"))
      (node (ref "ULN4") (pin "17") (pinfunction "17_17") (pintype "bidirectional"))
    )
    (net (code "125") (name "OUTD8") (class "Default")
      (node (ref "JP6") (pin "4") (pinfunction "4_4") (pintype "passive"))
      (node (ref "ULN4") (pin "18") (pinfunction "18_18") (pintype "bidirectional"))
    )
    (net (code "126") (name "OUTE1") (class "Default")
      (node (ref "JP6") (pin "6") (pinfunction "6_6") (pintype "passive"))
      (node (ref "ULN5") (pin "11") (pinfunction "11_11") (pintype "bidirectional"))
    )
    (net (code "127") (name "OUTE2") (class "Default")
      (node (ref "JP6") (pin "8") (pinfunction "8_8") (pintype "passive"))
      (node (ref "ULN5") (pin "12") (pinfunction "12_12") (pintype "bidirectional"))
    )
    (net (code "128") (name "OUTE3") (class "Default")
      (node (ref "JP6") (pin "10") (pinfunction "10_10") (pintype "passive"))
      (node (ref "ULN5") (pin "13") (pinfunction "13_13") (pintype "bidirectional"))
    )
    (net (code "129") (name "OUTE4") (class "Default")
      (node (ref "JP6") (pin "12") (pinfunction "12_12") (pintype "passive"))
      (node (ref "ULN5") (pin "14") (pinfunction "14_14") (pintype "bidirectional"))
    )
    (net (code "130") (name "OUTE5") (class "Default")
      (node (ref "JP6") (pin "14") (pinfunction "14_14") (pintype "passive"))
      (node (ref "ULN5") (pin "15") (pinfunction "15_15") (pintype "bidirectional"))
    )
    (net (code "131") (name "OUTE6") (class "Default")
      (node (ref "JP6") (pin "16") (pinfunction "16_16") (pintype "passive"))
      (node (ref "ULN5") (pin "16") (pinfunction "16_16") (pintype "bidirectional"))
    )
    (net (code "132") (name "OUTE7") (class "Default")
      (node (ref "JP6") (pin "18") (pinfunction "18_18") (pintype "passive"))
      (node (ref "ULN5") (pin "17") (pinfunction "17_17") (pintype "bidirectional"))
    )
    (net (code "133") (name "OUTE8") (class "Default")
      (node (ref "JP6") (pin "20") (pinfunction "20_20") (pintype "passive"))
      (node (ref "ULN5") (pin "18") (pinfunction "18_18") (pintype "bidirectional"))
    )
    (net (code "134") (name "PL") (class "Default")
      (node (ref "JP1") (pin "7") (pinfunction "7_7") (pintype "passive"))
      (node (ref "JP2") (pin "7") (pinfunction "7_7") (pintype "passive"))
      (node (ref "SHIFT1") (pin "1") (pinfunction "SH/~{LD}_1") (pintype "input"))
      (node (ref "SHIFT2") (pin "1") (pinfunction "SH/~{LD}_1") (pintype "input"))
      (node (ref "SHIFT3") (pin "1") (pinfunction "SH/~{LD}_1") (pintype "input"))
      (node (ref "SHIFT4") (pin "1") (pinfunction "SH/~{LD}_1") (pintype "input"))
      (node (ref "SHIFT5") (pin "1") (pinfunction "SH/~{LD}_1") (pintype "input"))
    )
    (net (code "135") (name "Q7") (class "Default")
      (node (ref "JP1") (pin "1") (pinfunction "1_1") (pintype "passive"))
      (node (ref "SHIFT1") (pin "9") (pinfunction "QH_9") (pintype "output"))
    )
    (net (code "136") (name "Q7_2") (class "Default")
      (node (ref "JP2") (pin "1") (pinfunction "1_1") (pintype "passive"))
      (node (ref "SHIFT5") (pin "10") (pinfunction "SER_10") (pintype "input"))
    )
    (net (code "137") (name "SHCP") (class "Default")
      (node (ref "JP1") (pin "8") (pinfunction "8_8") (pintype "passive"))
      (node (ref "JP2") (pin "8") (pinfunction "8_8") (pintype "passive"))
      (node (ref "SHIFTOUTA") (pin "11") (pinfunction "SCK_11") (pintype "input"))
      (node (ref "SHIFTOUTB") (pin "11") (pinfunction "SCK_11") (pintype "input"))
      (node (ref "SHIFTOUTC") (pin "11") (pinfunction "SCK_11") (pintype "input"))
      (node (ref "SHIFTOUTD") (pin "11") (pinfunction "SCK_11") (pintype "input"))
      (node (ref "SHIFTOUTE") (pin "11") (pinfunction "SCK_11") (pintype "input"))
    )
    (net (code "138") (name "SR_DS") (class "Default")
      (node (ref "JP1") (pin "4") (pinfunction "4_4") (pintype "passive"))
      (node (ref "SHIFTOUTA") (pin "14") (pinfunction "SER_14") (pintype "input"))
    )
    (net (code "139") (name "SR_DS_2") (class "Default")
      (node (ref "JP2") (pin "4") (pinfunction "4_4") (pintype "passive"))
      (node (ref "SHIFTOUTE") (pin "9") (pinfunction "QH*_9") (pintype "tri_state"))
    )
    (net (code "140") (name "STCP") (class "Default")
      (node (ref "JP1") (pin "6") (pinfunction "6_6") (pintype "passive"))
      (node (ref "JP2") (pin "6") (pinfunction "6_6") (pintype "passive"))
      (node (ref "SHIFTOUTA") (pin "12") (pinfunction "RCK_12") (pintype "input"))
      (node (ref "SHIFTOUTB") (pin "12") (pinfunction "RCK_12") (pintype "input"))
      (node (ref "SHIFTOUTC") (pin "12") (pinfunction "RCK_12") (pintype "input"))
      (node (ref "SHIFTOUTD") (pin "12") (pinfunction "RCK_12") (pintype "input"))
      (node (ref "SHIFTOUTE") (pin "12") (pinfunction "RCK_12") (pintype "input"))
    )
    (net (code "141") (name "VCC") (class "Default")
      (node (ref "J1") (pin "1") (pinfunction "1_1") (pintype "bidirectional"))
      (node (ref "J2") (pin "4") (pinfunction "4_4") (pintype "bidirectional"))
      (node (ref "RN1") (pin "1") (pinfunction "1_1") (pintype "passive"))
      (node (ref "RN2") (pin "1") (pinfunction "1_1") (pintype "passive"))
      (node (ref "RN3") (pin "1") (pinfunction "1_1") (pintype "passive"))
      (node (ref "RN4") (pin "1") (pinfunction "1_1") (pintype "passive"))
      (node (ref "RN5") (pin "1") (pinfunction "1_1") (pintype "passive"))
      (node (ref "SHIFT1") (pin "16") (pinfunction "VCC_16") (pintype "power_in"))
      (node (ref "SHIFT2") (pin "16") (pinfunction "VCC_16") (pintype "power_in"))
      (node (ref "SHIFT3") (pin "16") (pinfunction "VCC_16") (pintype "power_in"))
      (node (ref "SHIFT4") (pin "16") (pinfunction "VCC_16") (pintype "power_in"))
      (node (ref "SHIFT5") (pin "16") (pinfunction "VCC_16") (pintype "power_in"))
      (node (ref "SHIFTOUTA") (pin "16") (pinfunction "VCC_16") (pintype "power_in"))
      (node (ref "SHIFTOUTB") (pin "16") (pinfunction "VCC_16") (pintype "power_in"))
      (node (ref "SHIFTOUTC") (pin "16") (pinfunction "VCC_16") (pintype "power_in"))
      (node (ref "SHIFTOUTD") (pin "16") (pinfunction "VCC_16") (pintype "power_in"))
      (node (ref "SHIFTOUTE") (pin "16") (pinfunction "VCC_16") (pintype "power_in"))
    )
    (net (code "142") (name "unconnected-(SHIFT1A-~{QH}-Pad7)") (class "Default")
      (node (ref "SHIFT1") (pin "7") (pinfunction "~{QH}_7") (pintype "output"))
    )
    (net (code "143") (name "unconnected-(SHIFT2A-~{QH}-Pad7)") (class "Default")
      (node (ref "SHIFT2") (pin "7") (pinfunction "~{QH}_7") (pintype "output"))
    )
    (net (code "144") (name "unconnected-(SHIFT3A-~{QH}-Pad7)") (class "Default")
      (node (ref "SHIFT3") (pin "7") (pinfunction "~{QH}_7") (pintype "output"))
    )
    (net (code "145") (name "unconnected-(SHIFT4A-~{QH}-Pad7)") (class "Default")
      (node (ref "SHIFT4") (pin "7") (pinfunction "~{QH}_7") (pintype "output"))
    )
    (net (code "146") (name "unconnected-(SHIFT5A-~{QH}-Pad7)") (class "Default")
      (node (ref "SHIFT5") (pin "7") (pinfunction "~{QH}_7") (pintype "output"))
    )
  )
)
